# controller.net
KiCad netlist of a schematic drawn in EAGLE
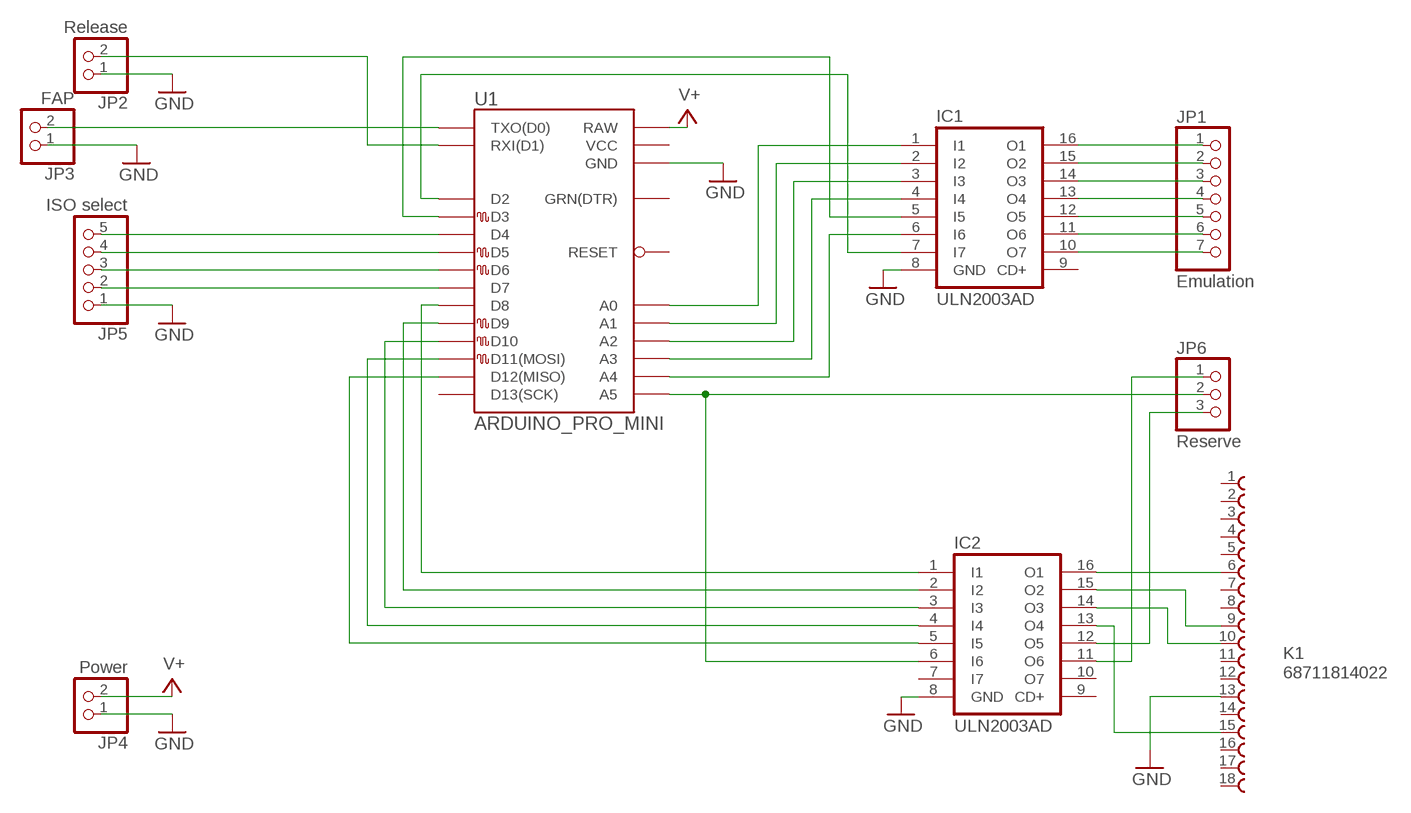
[diagram p0: schematic, sheet 1]

(export (version "E")
  (design (tool "Eeschema 10.0.6"))
  (components
    (comp (ref "IC1")
      (value "ULN2003AD")
      (footprint "eagle-import:SO16")
      (libsource (lib "eagle-import") (part "ULN2003AD"))
    )
    (comp (ref "IC2")
      (value "ULN2003AD")
      (footprint "eagle-import:SO16")
      (libsource (lib "eagle-import") (part "ULN2003AD"))
    )
    (comp (ref "JP1")
      (value "Emulation")
      (footprint "eagle-import:1X07_90")
      (libsource (lib "eagle-import") (part "PINHD-1X7/90"))
    )
    (comp (ref "JP2")
      (value "Release")
      (footprint "eagle-import:1X02")
      (libsource (lib "eagle-import") (part "PINHD-1X2"))
    )
    (comp (ref "JP3")
      (value "FAP")
      (footprint "eagle-import:1X02")
      (libsource (lib "eagle-import") (part "PINHD-1X2"))
    )
    (comp (ref "JP4")
      (value "Power")
      (footprint "eagle-import:1X02")
      (libsource (lib "eagle-import") (part "PINHD-1X2"))
    )
    (comp (ref "JP5")
      (value "ISO select")
      (footprint "eagle-import:1X05_90")
      (libsource (lib "eagle-import") (part "PINHD-1X5/90"))
    )
    (comp (ref "JP6")
      (value "Reserve")
      (footprint "eagle-import:1X03")
      (libsource (lib "eagle-import") (part "PINHD-1X3"))
    )
    (comp (ref "K1")
      (value "68711814022")
      (footprint "eagle-import:68711814022")
      (libsource (lib "eagle-import") (part "68711814022"))
    )
    (comp (ref "U1")
      (value "ARDUINO_PRO_MINI")
      (footprint "eagle-import:ARDUINO_PRO_MINI")
      (libsource (lib "eagle-import") (part "ARDUINO_PRO_MINI"))
    )
  )
  (nets
    (net (code "1") (name "GND") (class "Default")
      (node (ref "IC1") (pin "8") (pinfunction "GND_8") (pintype "power_in"))
      (node (ref "IC2") (pin "8") (pinfunction "GND_8") (pintype "power_in"))
      (node (ref "JP2") (pin "1") (pinfunction "1_1") (pintype "passive"))
      (node (ref "JP3") (pin "1") (pinfunction "1_1") (pintype "passive"))
      (node (ref "JP4") (pin "1") (pinfunction "1_1") (pintype "passive"))
      (node (ref "JP5") (pin "1") (pinfunction "1_1") (pintype "passive"))
      (node (ref "K1") (pin "13") (pinfunction "13_13") (pintype "passive"))
      (node (ref "U1") (pin "GND1") (pinfunction "GND_GND1") (pintype "bidirectional"))
    )
    (net (code "2") (name "Net-(IC1-I1)") (class "Default")
      (node (ref "IC1") (pin "1") (pinfunction "I1_1") (pintype "input"))
      (node (ref "U1") (pin "A0") (pinfunction "A0_A0") (pintype "bidirectional"))
    )
    (net (code "3") (name "Net-(IC1-I2)") (class "Default")
      (node (ref "IC1") (pin "2") (pinfunction "I2_2") (pintype "input"))
      (node (ref "U1") (pin "A1") (pinfunction "A1_A1") (pintype "bidirectional"))
    )
    (net (code "4") (name "Net-(IC1-I3)") (class "Default")
      (node (ref "IC1") (pin "3") (pinfunction "I3_3") (pintype "input"))
      (node (ref "U1") (pin "A2") (pinfunction "A2_A2") (pintype "bidirectional"))
    )
    (net (code "5") (name "Net-(IC1-I4)") (class "Default")
      (node (ref "IC1") (pin "4") (pinfunction "I4_4") (pintype "input"))
      (node (ref "U1") (pin "A3") (pinfunction "A3_A3") (pintype "bidirectional"))
    )
    (net (code "6") (name "Net-(IC1-I5)") (class "Default")
      (node (ref "IC1") (pin "5") (pinfunction "I5_5") (pintype "input"))
      (node (ref "U1") (pin "D3") (pinfunction "D3_D3") (pintype "bidirectional"))
    )
    (net (code "7") (name "Net-(IC1-I6)") (class "Default")
      (node (ref "IC1") (pin "6") (pinfunction "I6_6") (pintype "input"))
      (node (ref "U1") (pin "A4") (pinfunction "A4_A4") (pintype "bidirectional"))
    )
    (net (code "8") (name "Net-(IC1-I7)") (class "Default")
      (node (ref "IC1") (pin "7") (pinfunction "I7_7") (pintype "input"))
      (node (ref "U1") (pin "D2") (pinfunction "D2_D2") (pintype "bidirectional"))
    )
    (net (code "9") (name "Net-(IC1-O1)") (class "Default")
      (node (ref "IC1") (pin "16") (pinfunction "O1_16") (pintype "open_collector"))
      (node (ref "JP1") (pin "1") (pinfunction "1_1") (pintype "passive"))
    )
    (net (code "10") (name "Net-(IC1-O2)") (class "Default")
      (node (ref "IC1") (pin "15") (pinfunction "O2_15") (pintype "open_collector"))
      (node (ref "JP1") (pin "2") (pinfunction "2_2") (pintype "passive"))
    )
    (net (code "11") (name "Net-(IC1-O3)") (class "Default")
      (node (ref "IC1") (pin "14") (pinfunction "O3_14") (pintype "open_collector"))
      (node (ref "JP1") (pin "3") (pinfunction "3_3") (pintype "passive"))
    )
    (net (code "12") (name "Net-(IC1-O4)") (class "Default")
      (node (ref "IC1") (pin "13") (pinfunction "O4_13") (pintype "open_collector"))
      (node (ref "JP1") (pin "4") (pinfunction "4_4") (pintype "passive"))
    )
    (net (code "13") (name "Net-(IC1-O5)") (class "Default")
      (node (ref "IC1") (pin "12") (pinfunction "O5_12") (pintype "open_collector"))
      (node (ref "JP1") (pin "5") (pinfunction "5_5") (pintype "passive"))
    )
    (net (code "14") (name "Net-(IC1-O6)") (class "Default")
      (node (ref "IC1") (pin "11") (pinfunction "O6_11") (pintype "open_collector"))
      (node (ref "JP1") (pin "6") (pinfunction "6_6") (pintype "passive"))
    )
    (net (code "15") (name "Net-(IC1-O7)") (class "Default")
      (node (ref "IC1") (pin "10") (pinfunction "O7_10") (pintype "open_collector"))
      (node (ref "JP1") (pin "7") (pinfunction "7_7") (pintype "passive"))
    )
    (net (code "16") (name "Net-(IC2-I1)") (class "Default")
      (node (ref "IC2") (pin "1") (pinfunction "I1_1") (pintype "input"))
      (node (ref "U1") (pin "D8") (pinfunction "D8_D8") (pintype "bidirectional"))
    )
    (net (code "17") (name "Net-(IC2-I2)") (class "Default")
      (node (ref "IC2") (pin "2") (pinfunction "I2_2") (pintype "input"))
      (node (ref "U1") (pin "D9") (pinfunction "D9_D9") (pintype "bidirectional"))
    )
    (net (code "18") (name "Net-(IC2-I3)") (class "Default")
      (node (ref "IC2") (pin "3") (pinfunction "I3_3") (pintype "input"))
      (node (ref "U1") (pin "D10") (pinfunction "D10_D10") (pintype "bidirectional"))
    )
    (net (code "19") (name "Net-(IC2-I4)") (class "Default")
      (node (ref "IC2") (pin "4") (pinfunction "I4_4") (pintype "input"))
      (node (ref "U1") (pin "D11") (pinfunction "D11(MOSI)_D11") (pintype "bidirectional"))
    )
    (net (code "20") (name "Net-(IC2-I5)") (class "Default")
      (node (ref "IC2") (pin "5") (pinfunction "I5_5") (pintype "input"))
      (node (ref "U1") (pin "D12") (pinfunction "D12(MISO)_D12") (pintype "bidirectional"))
    )
    (net (code "21") (name "Net-(IC2-I6)") (class "Default")
      (node (ref "IC2") (pin "6") (pinfunction "I6_6") (pintype "input"))
      (node (ref "JP6") (pin "2") (pinfunction "2_2") (pintype "passive"))
      (node (ref "U1") (pin "A5") (pinfunction "A5_A5") (pintype "bidirectional"))
    )
    (net (code "22") (name "Net-(IC2-O1)") (class "Default")
      (node (ref "IC2") (pin "16") (pinfunction "O1_16") (pintype "open_collector"))
      (node (ref "K1") (pin "6") (pinfunction "6_6") (pintype "passive"))
    )
    (net (code "23") (name "Net-(IC2-O2)") (class "Default")
      (node (ref "IC2") (pin "15") (pinfunction "O2_15") (pintype "open_collector"))
      (node (ref "K1") (pin "9") (pinfunction "9_9") (pintype "passive"))
    )
    (net (code "24") (name "Net-(IC2-O3)") (class "Default")
      (node (ref "IC2") (pin "14") (pinfunction "O3_14") (pintype "open_collector"))
      (node (ref "K1") (pin "10") (pinfunction "10_10") (pintype "passive"))
    )
    (net (code "25") (name "Net-(IC2-O4)") (class "Default")
      (node (ref "IC2") (pin "13") (pinfunction "O4_13") (pintype "open_collector"))
      (node (ref "K1") (pin "15") (pinfunction "15_15") (pintype "passive"))
    )
    (net (code "26") (name "Net-(IC2-O5)") (class "Default")
      (node (ref "IC2") (pin "12") (pinfunction "O5_12") (pintype "open_collector"))
      (node (ref "JP6") (pin "3") (pinfunction "3_3") (pintype "passive"))
    )
    (net (code "27") (name "Net-(IC2-O6)") (class "Default")
      (node (ref "IC2") (pin "11") (pinfunction "O6_11") (pintype "open_collector"))
      (node (ref "JP6") (pin "1") (pinfunction "1_1") (pintype "passive"))
    )
    (net (code "28") (name "Net-(JP5-Pad2)") (class "Default")
      (node (ref "JP5") (pin "2") (pinfunction "2_2") (pintype "passive"))
      (node (ref "U1") (pin "D7") (pinfunction "D7_D7") (pintype "bidirectional"))
    )
    (net (code "29") (name "Net-(JP5-Pad3)") (class "Default")
      (node (ref "JP5") (pin "3") (pinfunction "3_3") (pintype "passive"))
      (node (ref "U1") (pin "D6") (pinfunction "D6_D6") (pintype "bidirectional"))
    )
    (net (code "30") (name "Net-(JP5-Pad4)") (class "Default")
      (node (ref "JP5") (pin "4") (pinfunction "4_4") (pintype "passive"))
      (node (ref "U1") (pin "D5") (pinfunction "D5_D5") (pintype "bidirectional"))
    )
    (net (code "31") (name "Net-(JP5-Pad5)") (class "Default")
      (node (ref "JP5") (pin "5") (pinfunction "5_5") (pintype "passive"))
      (node (ref "U1") (pin "D4") (pinfunction "D4_D4") (pintype "bidirectional"))
    )
    (net (code "32") (name "Net-(U1-RXI(D1))") (class "Default")
      (node (ref "JP2") (pin "2") (pinfunction "2_2") (pintype "passive"))
      (node (ref "U1") (pin "RXI") (pinfunction "RXI(D1)_RXI") (pintype "bidirectional"))
    )
    (net (code "33") (name "Net-(U1-TXO(D0))") (class "Default")
      (node (ref "JP3") (pin "2") (pinfunction "2_2") (pintype "passive"))
      (node (ref "U1") (pin "TXO") (pinfunction "TXO(D0)_TXO") (pintype "bidirectional"))
    )
    (net (code "34") (name "V+") (class "Default")
      (node (ref "JP4") (pin "2") (pinfunction "2_2") (pintype "passive"))
      (node (ref "U1") (pin "RAW") (pinfunction "RAW_RAW") (pintype "bidirectional"))
    )
    (net (code "35") (name "unconnected-(IC1-CD+-Pad9)") (class "Default")
      (node (ref "IC1") (pin "9") (pinfunction "CD+_9") (pintype "passive"))
    )
    (net (code "36") (name "unconnected-(IC2-CD+-Pad9)") (class "Default")
      (node (ref "IC2") (pin "9") (pinfunction "CD+_9") (pintype "passive"))
    )
    (net (code "37") (name "unconnected-(IC2-I7-Pad7)") (class "Default")
      (node (ref "IC2") (pin "7") (pinfunction "I7_7") (pintype "input"))
    )
    (net (code "38") (name "unconnected-(IC2-O7-Pad10)") (class "Default")
      (node (ref "IC2") (pin "10") (pinfunction "O7_10") (pintype "open_collector"))
    )
    (net (code "39") (name "unconnected-(K1-Pad1)") (class "Default")
      (node (ref "K1") (pin "1") (pinfunction "1_1") (pintype "passive"))
    )
    (net (code "40") (name "unconnected-(K1-Pad2)") (class "Default")
      (node (ref "K1") (pin "2") (pinfunction "2_2") (pintype "passive"))
    )
    (net (code "41") (name "unconnected-(K1-Pad3)") (class "Default")
      (node (ref "K1") (pin "3") (pinfunction "3_3") (pintype "passive"))
    )
    (net (code "42") (name "unconnected-(K1-Pad4)") (class "Default")
      (node (ref "K1") (pin "4") (pinfunction "4_4") (pintype "passive"))
    )
    (net (code "43") (name "unconnected-(K1-Pad5)") (class "Default")
      (node (ref "K1") (pin "5") (pinfunction "5_5") (pintype "passive"))
    )
    (net (code "44") (name "unconnected-(K1-Pad7)") (class "Default")
      (node (ref "K1") (pin "7") (pinfunction "7_7") (pintype "passive"))
    )
    (net (code "45") (name "unconnected-(K1-Pad8)") (class "Default")
      (node (ref "K1") (pin "8") (pinfunction "8_8") (pintype "passive"))
    )
    (net (code "46") (name "unconnected-(K1-Pad11)") (class "Default")
      (node (ref "K1") (pin "11") (pinfunction "11_11") (pintype "passive"))
    )
    (net (code "47") (name "unconnected-(K1-Pad12)") (class "Default")
      (node (ref "K1") (pin "12") (pinfunction "12_12") (pintype "passive"))
    )
    (net (code "48") (name "unconnected-(K1-Pad14)") (class "Default")
      (node (ref "K1") (pin "14") (pinfunction "14_14") (pintype "passive"))
    )
    (net (code "49") (name "unconnected-(K1-Pad16)") (class "Default")
      (node (ref "K1") (pin "16") (pinfunction "16_16") (pintype "passive"))
    )
    (net (code "50") (name "unconnected-(K1-Pad17)") (class "Default")
      (node (ref "K1") (pin "17") (pinfunction "17_17") (pintype "passive"))
    )
    (net (code "51") (name "unconnected-(K1-Pad18)") (class "Default")
      (node (ref "K1") (pin "18") (pinfunction "18_18") (pintype "passive"))
    )
    (net (code "52") (name "unconnected-(U1-D13(SCK)-PadD13)") (class "Default")
      (node (ref "U1") (pin "D13") (pinfunction "D13(SCK)_D13") (pintype "bidirectional"))
    )
    (net (code "53") (name "unconnected-(U1-GRN(DTR)-PadGRN)") (class "Default")
      (node (ref "U1") (pin "GRN") (pinfunction "GRN(DTR)_GRN") (pintype "bidirectional"))
    )
    (net (code "54") (name "unconnected-(U1-RESET-PadRST1)") (class "Default")
      (node (ref "U1") (pin "RST1") (pinfunction "RESET_RST1") (pintype "bidirectional"))
    )
    (net (code "55") (name "unconnected-(U1-VCC-PadVCC1)") (class "Default")
      (node (ref "U1") (pin "VCC1") (pinfunction "VCC_VCC1") (pintype "bidirectional"))
    )
  )
)
